# ATM9036_3P4W.net
KiCad netlist of a schematic drawn in EAGLE
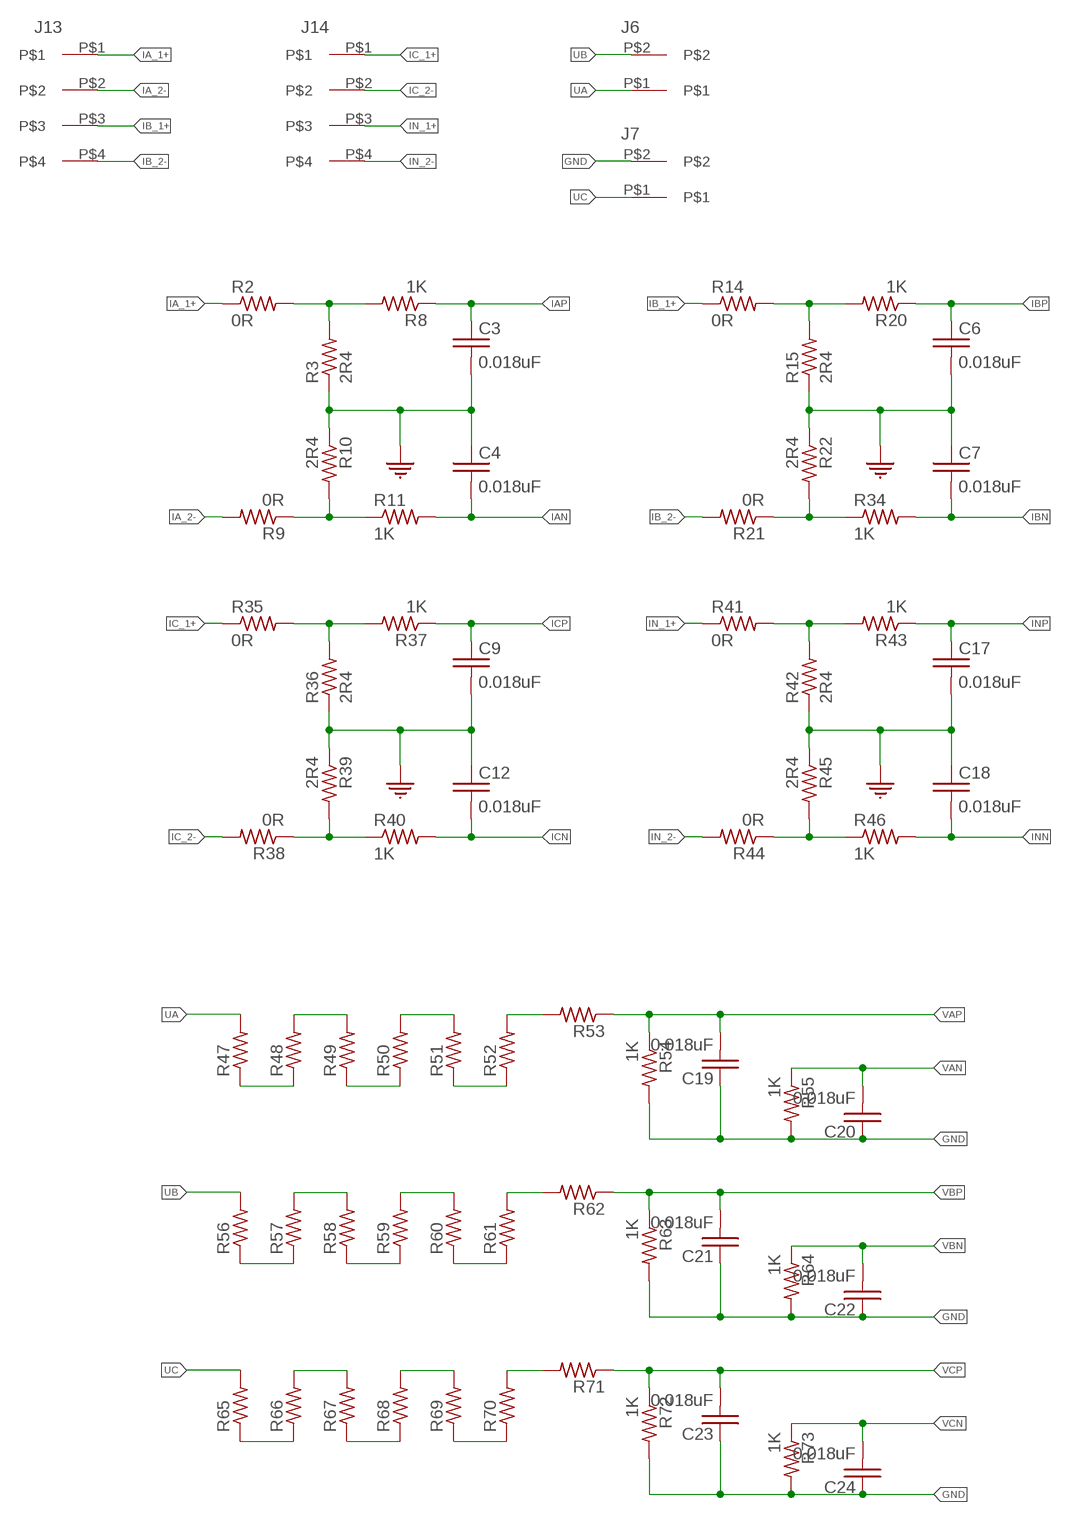
[diagram p0: schematic, sheet 1, part 1 of 2]
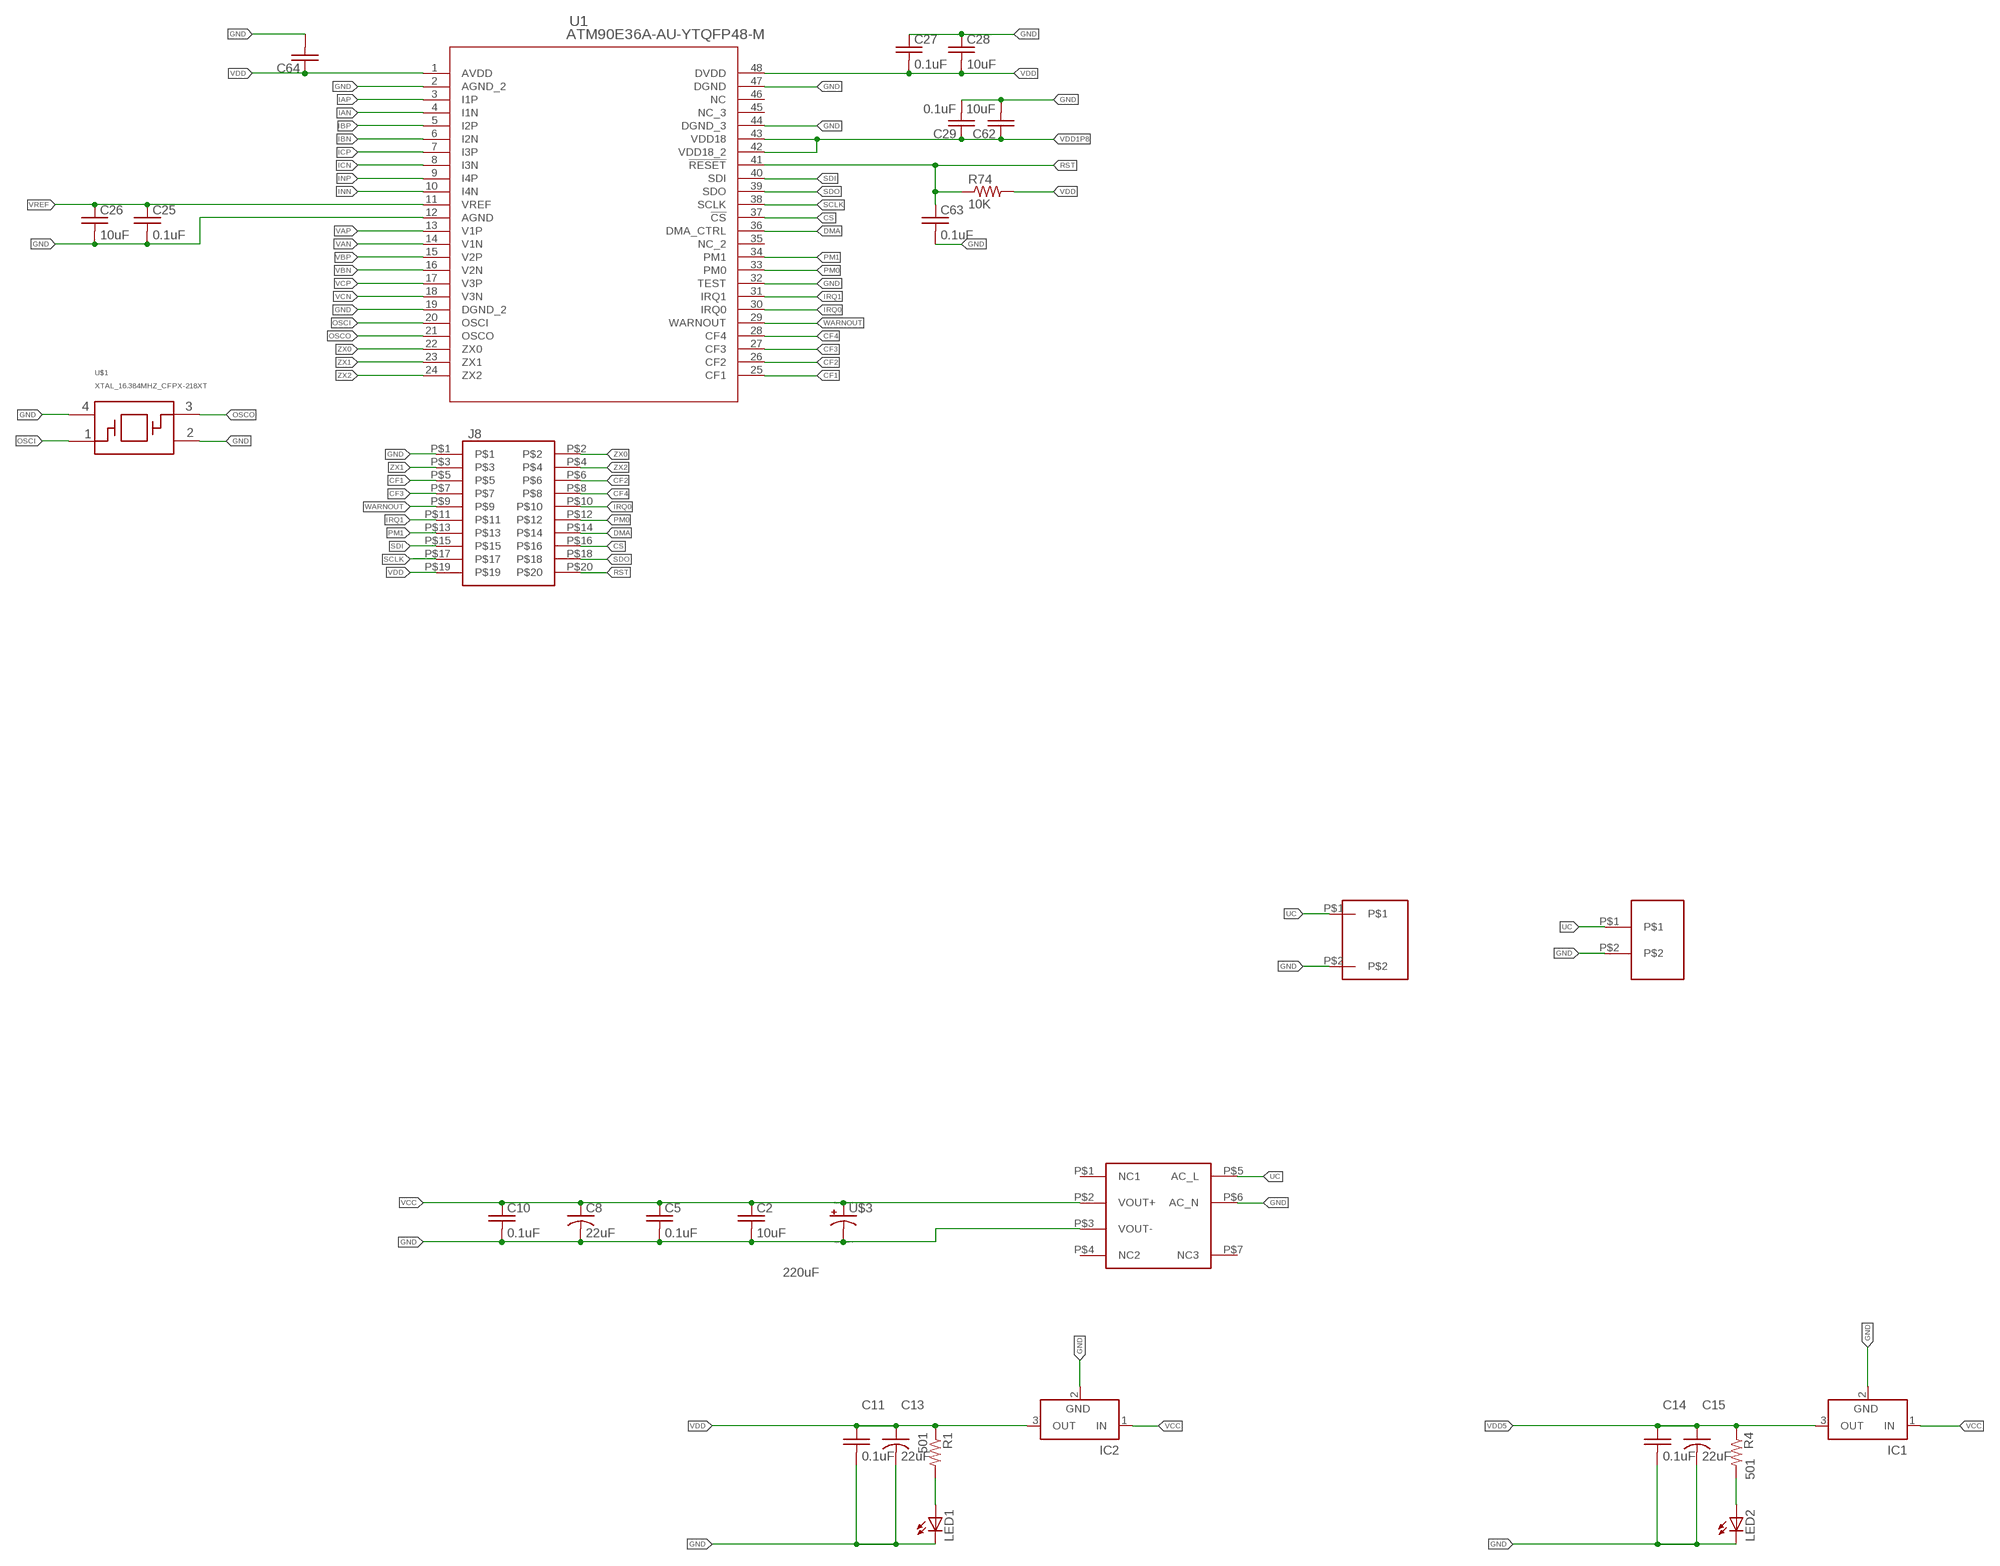
[diagram p1: schematic, sheet 1, part 2 of 2]

(export (version "E")
  (design (tool "Eeschema 10.0.6"))
  (components
    (comp (ref "C1")
      (value "CAP_THIN_FILM_TDK_32922CAP")
      (footprint "eagle-import:CAP_THIN_FILM_32922")
      (libsource (lib "eagle-import") (part "CAP_THIN_FILM_TDK_32922CAP"))
    )
    (comp (ref "C2")
      (value "10uF")
      (footprint "eagle-import:0402")
      (libsource (lib "eagle-import") (part "C_0402"))
    )
    (comp (ref "C3")
      (value "0.018uF")
      (footprint "eagle-import:0402")
      (libsource (lib "eagle-import") (part "C_0402"))
    )
    (comp (ref "C4")
      (value "0.018uF")
      (footprint "eagle-import:0402")
      (libsource (lib "eagle-import") (part "C_0402"))
    )
    (comp (ref "C5")
      (value "0.1uF")
      (footprint "eagle-import:0402")
      (libsource (lib "eagle-import") (part "C_0402"))
    )
    (comp (ref "C6")
      (value "0.018uF")
      (footprint "eagle-import:0402")
      (libsource (lib "eagle-import") (part "C_0402"))
    )
    (comp (ref "C7")
      (value "0.018uF")
      (footprint "eagle-import:0402")
      (libsource (lib "eagle-import") (part "C_0402"))
    )
    (comp (ref "C8")
      (value "22uF")
      (footprint "eagle-import:C1206")
      (libsource (lib "eagle-import") (part "C-USC1206"))
    )
    (comp (ref "C9")
      (value "0.018uF")
      (footprint "eagle-import:0402")
      (libsource (lib "eagle-import") (part "C_0402"))
    )
    (comp (ref "C10")
      (value "0.1uF")
      (footprint "eagle-import:0402")
      (libsource (lib "eagle-import") (part "C_0402"))
    )
    (comp (ref "C11")
      (value "0.1uF")
      (footprint "eagle-import:0402")
      (libsource (lib "eagle-import") (part "C_0402"))
    )
    (comp (ref "C12")
      (value "0.018uF")
      (footprint "eagle-import:0402")
      (libsource (lib "eagle-import") (part "C_0402"))
    )
    (comp (ref "C13")
      (value "22uF")
      (footprint "eagle-import:C1206")
      (libsource (lib "eagle-import") (part "C-USC1206"))
    )
    (comp (ref "C14")
      (value "0.1uF")
      (footprint "eagle-import:0402")
      (libsource (lib "eagle-import") (part "C_0402"))
    )
    (comp (ref "C15")
      (value "22uF")
      (footprint "eagle-import:C1206")
      (libsource (lib "eagle-import") (part "C-USC1206"))
    )
    (comp (ref "C17")
      (value "0.018uF")
      (footprint "eagle-import:0402")
      (libsource (lib "eagle-import") (part "C_0402"))
    )
    (comp (ref "C18")
      (value "0.018uF")
      (footprint "eagle-import:0402")
      (libsource (lib "eagle-import") (part "C_0402"))
    )
    (comp (ref "C19")
      (value "0.018uF")
      (footprint "eagle-import:0402")
      (libsource (lib "eagle-import") (part "C_0402"))
    )
    (comp (ref "C20")
      (value "0.018uF")
      (footprint "eagle-import:0402")
      (libsource (lib "eagle-import") (part "C_0402"))
    )
    (comp (ref "C21")
      (value "0.018uF")
      (footprint "eagle-import:0402")
      (libsource (lib "eagle-import") (part "C_0402"))
    )
    (comp (ref "C22")
      (value "0.018uF")
      (footprint "eagle-import:0402")
      (libsource (lib "eagle-import") (part "C_0402"))
    )
    (comp (ref "C23")
      (value "0.018uF")
      (footprint "eagle-import:0402")
      (libsource (lib "eagle-import") (part "C_0402"))
    )
    (comp (ref "C24")
      (value "0.018uF")
      (footprint "eagle-import:0402")
      (libsource (lib "eagle-import") (part "C_0402"))
    )
    (comp (ref "C25")
      (value "0.1uF")
      (footprint "eagle-import:0402")
      (libsource (lib "eagle-import") (part "C_0402"))
    )
    (comp (ref "C26")
      (value "10uF")
      (footprint "eagle-import:0402")
      (libsource (lib "eagle-import") (part "C_0402"))
    )
    (comp (ref "C27")
      (value "0.1uF")
      (footprint "eagle-import:0402")
      (libsource (lib "eagle-import") (part "C_0402"))
    )
    (comp (ref "C28")
      (value "10uF")
      (footprint "eagle-import:0402")
      (libsource (lib "eagle-import") (part "C_0402"))
    )
    (comp (ref "C29")
      (value "0.1uF")
      (footprint "eagle-import:0402")
      (libsource (lib "eagle-import") (part "C_0402"))
    )
    (comp (ref "C62")
      (value "10uF")
      (footprint "eagle-import:0402")
      (libsource (lib "eagle-import") (part "C_0402"))
    )
    (comp (ref "C63")
      (value "0.1uF")
      (footprint "eagle-import:0402")
      (libsource (lib "eagle-import") (part "C_0402"))
    )
    (comp (ref "C64")
      (value "C_0402")
      (footprint "eagle-import:0402")
      (libsource (lib "eagle-import") (part "C_0402"))
    )
    (comp (ref "IC1")
      (value "LT1129CST5")
      (footprint "eagle-import:SOT223")
      (fields (field (name "MPN") "LT1129CST-5#PBF"))
      (libsource (lib "eagle-import") (part "LT1129CST5"))
    )
    (comp (ref "IC2")
      (value "LT1129CST3")
      (footprint "eagle-import:SOT223")
      (fields (field (name "MPN") "LT1129CST-5#PBF"))
      (libsource (lib "eagle-import") (part "LT1129CST3"))
    )
    (comp (ref "J6")
      (value "3.81MM_1_X_2_RT_ANGLE_PLUG_HEADER")
      (footprint "eagle-import:2_3.81MM_PITCH")
      (libsource (lib "eagle-import") (part "3.81MM_1_X_2_RT_ANGLE_PLUG_HEADER"))
    )
    (comp (ref "J7")
      (value "3.81MM_1_X_2_RT_ANGLE_PLUG_HEADER")
      (footprint "eagle-import:2_3.81MM_PITCH")
      (libsource (lib "eagle-import") (part "3.81MM_1_X_2_RT_ANGLE_PLUG_HEADER"))
    )
    (comp (ref "J8")
      (value "2_X_10_HEADER_GENERIC")
      (footprint "eagle-import:2_X_10_.1_INCH")
      (libsource (lib "eagle-import") (part "2_X_10_HEADER_GENERIC"))
    )
    (comp (ref "J13")
      (value "3.81MM_1_X_4_RT_ANGLE_PLUG_HEADER")
      (footprint "eagle-import:1X4_3.81MM_PITCH")
      (libsource (lib "eagle-import") (part "3.81MM_1_X_4_RT_ANGLE_PLUG_HEADER"))
    )
    (comp (ref "J14")
      (value "3.81MM_1_X_4_RT_ANGLE_PLUG_HEADER")
      (footprint "eagle-import:1X4_3.81MM_PITCH")
      (libsource (lib "eagle-import") (part "3.81MM_1_X_4_RT_ANGLE_PLUG_HEADER"))
    )
    (comp (ref "LED1")
      (value "LED_0805_GREEN")
      (footprint "eagle-import:LED_0805_GREEN")
      (libsource (lib "eagle-import") (part "LED_0805_GREEN"))
    )
    (comp (ref "LED2")
      (value "LED_0805_GREEN")
      (footprint "eagle-import:LED_0805_GREEN")
      (libsource (lib "eagle-import") (part "LED_0805_GREEN"))
    )
    (comp (ref "R1")
      (value "501")
      (footprint "eagle-import:0402")
      (libsource (lib "eagle-import") (part "R_0402"))
    )
    (comp (ref "R2")
      (value "0R")
      (footprint "eagle-import:0402")
      (libsource (lib "eagle-import") (part "R_0402"))
    )
    (comp (ref "R3")
      (value "2R4")
      (footprint "eagle-import:0402")
      (libsource (lib "eagle-import") (part "R_0402"))
    )
    (comp (ref "R4")
      (value "501")
      (footprint "eagle-import:0402")
      (libsource (lib "eagle-import") (part "R_0402"))
    )
    (comp (ref "R8")
      (value "1K")
      (footprint "eagle-import:0402")
      (libsource (lib "eagle-import") (part "R_0402"))
    )
    (comp (ref "R9")
      (value "0R")
      (footprint "eagle-import:0402")
      (libsource (lib "eagle-import") (part "R_0402"))
    )
    (comp (ref "R10")
      (value "2R4")
      (footprint "eagle-import:0402")
      (libsource (lib "eagle-import") (part "R_0402"))
    )
    (comp (ref "R11")
      (value "1K")
      (footprint "eagle-import:0402")
      (libsource (lib "eagle-import") (part "R_0402"))
    )
    (comp (ref "R14")
      (value "0R")
      (footprint "eagle-import:0402")
      (libsource (lib "eagle-import") (part "R_0402"))
    )
    (comp (ref "R15")
      (value "2R4")
      (footprint "eagle-import:0402")
      (libsource (lib "eagle-import") (part "R_0402"))
    )
    (comp (ref "R20")
      (value "1K")
      (footprint "eagle-import:0402")
      (libsource (lib "eagle-import") (part "R_0402"))
    )
    (comp (ref "R21")
      (value "0R")
      (footprint "eagle-import:0402")
      (libsource (lib "eagle-import") (part "R_0402"))
    )
    (comp (ref "R22")
      (value "2R4")
      (footprint "eagle-import:0402")
      (libsource (lib "eagle-import") (part "R_0402"))
    )
    (comp (ref "R34")
      (value "1K")
      (footprint "eagle-import:0402")
      (libsource (lib "eagle-import") (part "R_0402"))
    )
    (comp (ref "R35")
      (value "0R")
      (footprint "eagle-import:0402")
      (libsource (lib "eagle-import") (part "R_0402"))
    )
    (comp (ref "R36")
      (value "2R4")
      (footprint "eagle-import:0402")
      (libsource (lib "eagle-import") (part "R_0402"))
    )
    (comp (ref "R37")
      (value "1K")
      (footprint "eagle-import:0402")
      (libsource (lib "eagle-import") (part "R_0402"))
    )
    (comp (ref "R38")
      (value "0R")
      (footprint "eagle-import:0402")
      (libsource (lib "eagle-import") (part "R_0402"))
    )
    (comp (ref "R39")
      (value "2R4")
      (footprint "eagle-import:0402")
      (libsource (lib "eagle-import") (part "R_0402"))
    )
    (comp (ref "R40")
      (value "1K")
      (footprint "eagle-import:0402")
      (libsource (lib "eagle-import") (part "R_0402"))
    )
    (comp (ref "R41")
      (value "0R")
      (footprint "eagle-import:0402")
      (libsource (lib "eagle-import") (part "R_0402"))
    )
    (comp (ref "R42")
      (value "2R4")
      (footprint "eagle-import:0402")
      (libsource (lib "eagle-import") (part "R_0402"))
    )
    (comp (ref "R43")
      (value "1K")
      (footprint "eagle-import:0402")
      (libsource (lib "eagle-import") (part "R_0402"))
    )
    (comp (ref "R44")
      (value "0R")
      (footprint "eagle-import:0402")
      (libsource (lib "eagle-import") (part "R_0402"))
    )
    (comp (ref "R45")
      (value "2R4")
      (footprint "eagle-import:0402")
      (libsource (lib "eagle-import") (part "R_0402"))
    )
    (comp (ref "R46")
      (value "1K")
      (footprint "eagle-import:0402")
      (libsource (lib "eagle-import") (part "R_0402"))
    )
    (comp (ref "R47")
      (value "R_0402")
      (footprint "eagle-import:0402")
      (libsource (lib "eagle-import") (part "R_0402"))
    )
    (comp (ref "R48")
      (value "R_0402")
      (footprint "eagle-import:0402")
      (libsource (lib "eagle-import") (part "R_0402"))
    )
    (comp (ref "R49")
      (value "R_0402")
      (footprint "eagle-import:0402")
      (libsource (lib "eagle-import") (part "R_0402"))
    )
    (comp (ref "R50")
      (value "R_0402")
      (footprint "eagle-import:0402")
      (libsource (lib "eagle-import") (part "R_0402"))
    )
    (comp (ref "R51")
      (value "R_0402")
      (footprint "eagle-import:0402")
      (libsource (lib "eagle-import") (part "R_0402"))
    )
    (comp (ref "R52")
      (value "R_0402")
      (footprint "eagle-import:0402")
      (libsource (lib "eagle-import") (part "R_0402"))
    )
    (comp (ref "R53")
      (value "R_0402")
      (footprint "eagle-import:0402")
      (libsource (lib "eagle-import") (part "R_0402"))
    )
    (comp (ref "R54")
      (value "1K")
      (footprint "eagle-import:0402")
      (libsource (lib "eagle-import") (part "R_0402"))
    )
    (comp (ref "R55")
      (value "1K")
      (footprint "eagle-import:0402")
      (libsource (lib "eagle-import") (part "R_0402"))
    )
    (comp (ref "R56")
      (value "R_0402")
      (footprint "eagle-import:0402")
      (libsource (lib "eagle-import") (part "R_0402"))
    )
    (comp (ref "R57")
      (value "R_0402")
      (footprint "eagle-import:0402")
      (libsource (lib "eagle-import") (part "R_0402"))
    )
    (comp (ref "R58")
      (value "R_0402")
      (footprint "eagle-import:0402")
      (libsource (lib "eagle-import") (part "R_0402"))
    )
    (comp (ref "R59")
      (value "R_0402")
      (footprint "eagle-import:0402")
      (libsource (lib "eagle-import") (part "R_0402"))
    )
    (comp (ref "R60")
      (value "R_0402")
      (footprint "eagle-import:0402")
      (libsource (lib "eagle-import") (part "R_0402"))
    )
    (comp (ref "R61")
      (value "R_0402")
      (footprint "eagle-import:0402")
      (libsource (lib "eagle-import") (part "R_0402"))
    )
    (comp (ref "R62")
      (value "R_0402")
      (footprint "eagle-import:0402")
      (libsource (lib "eagle-import") (part "R_0402"))
    )
    (comp (ref "R63")
      (value "1K")
      (footprint "eagle-import:0402")
      (libsource (lib "eagle-import") (part "R_0402"))
    )
    (comp (ref "R64")
      (value "1K")
      (footprint "eagle-import:0402")
      (libsource (lib "eagle-import") (part "R_0402"))
    )
    (comp (ref "R65")
      (value "R_0402")
      (footprint "eagle-import:0402")
      (libsource (lib "eagle-import") (part "R_0402"))
    )
    (comp (ref "R66")
      (value "R_0402")
      (footprint "eagle-import:0402")
      (libsource (lib "eagle-import") (part "R_0402"))
    )
    (comp (ref "R67")
      (value "R_0402")
      (footprint "eagle-import:0402")
      (libsource (lib "eagle-import") (part "R_0402"))
    )
    (comp (ref "R68")
      (value "R_0402")
      (footprint "eagle-import:0402")
      (libsource (lib "eagle-import") (part "R_0402"))
    )
    (comp (ref "R69")
      (value "R_0402")
      (footprint "eagle-import:0402")
      (libsource (lib "eagle-import") (part "R_0402"))
    )
    (comp (ref "R70")
      (value "R_0402")
      (footprint "eagle-import:0402")
      (libsource (lib "eagle-import") (part "R_0402"))
    )
    (comp (ref "R71")
      (value "R_0402")
      (footprint "eagle-import:0402")
      (libsource (lib "eagle-import") (part "R_0402"))
    )
    (comp (ref "R72")
      (value "1K")
      (footprint "eagle-import:0402")
      (libsource (lib "eagle-import") (part "R_0402"))
    )
    (comp (ref "R73")
      (value "1K")
      (footprint "eagle-import:0402")
      (libsource (lib "eagle-import") (part "R_0402"))
    )
    (comp (ref "R74")
      (value "10K")
      (footprint "eagle-import:0402")
      (libsource (lib "eagle-import") (part "R_0402"))
    )
    (comp (ref "U$1")
      (value "XTAL_16.384MHZ_CFPX-218XT")
      (footprint "eagle-import:XTAL_2.5X2.0")
      (libsource (lib "eagle-import") (part "XTAL_16.384MHZ_CFPX-218XT"))
    )
    (comp (ref "U$2")
      (value "VAR_10MM_VDRUS10")
      (footprint "eagle-import:VAR_10MM_VDRUS10")
      (libsource (lib "eagle-import") (part "VAR_10MM_VDRUS10"))
    )
    (comp (ref "U$3")
      (value "220uF")
      (footprint "eagle-import:C_AL_ELECTROLYTIC_SMD_220UF")
      (libsource (lib "eagle-import") (part "C_AL_ELECTROLYTIC_SMD_220UF"))
    )
    (comp (ref "U1")
      (value "ATM90E36A-AU-YTQFP48-M")
      (footprint "eagle-import:TQFP48-M")
      (fields (field (name "MANUFACTURER_PART_NUMBER") "ATM90E36AAUY"))
      (libsource (lib "eagle-import") (part "ATM90E36A-AU-YTQFP48-M"))
    )
    (comp (ref "U2")
      (value "TMLM_04109")
      (footprint "eagle-import:TMLM04")
      (libsource (lib "eagle-import") (part "TMLM_04109"))
    )
  )
  (nets
    (net (code "1") (name "CF1") (class "Default")
      (node (ref "J8") (pin "P$5") (pinfunction "P$5_P$5") (pintype "bidirectional"))
      (node (ref "U1") (pin "25") (pinfunction "CF1_25") (pintype "output"))
    )
    (net (code "2") (name "CF2") (class "Default")
      (node (ref "J8") (pin "P$6") (pinfunction "P$6_P$6") (pintype "bidirectional"))
      (node (ref "U1") (pin "26") (pinfunction "CF2_26") (pintype "output"))
    )
    (net (code "3") (name "CF3") (class "Default")
      (node (ref "J8") (pin "P$7") (pinfunction "P$7_P$7") (pintype "bidirectional"))
      (node (ref "U1") (pin "27") (pinfunction "CF3_27") (pintype "output"))
    )
    (net (code "4") (name "CF4") (class "Default")
      (node (ref "J8") (pin "P$8") (pinfunction "P$8_P$8") (pintype "bidirectional"))
      (node (ref "U1") (pin "28") (pinfunction "CF4_28") (pintype "output"))
    )
    (net (code "5") (name "CS") (class "Default")
      (node (ref "J8") (pin "P$16") (pinfunction "P$16_P$16") (pintype "bidirectional"))
      (node (ref "U1") (pin "37") (pinfunction "~{CS}_37") (pintype "bidirectional"))
    )
    (net (code "6") (name "DMA") (class "Default")
      (node (ref "J8") (pin "P$14") (pinfunction "P$14_P$14") (pintype "bidirectional"))
      (node (ref "U1") (pin "36") (pinfunction "DMA_CTRL_36") (pintype "input"))
    )
    (net (code "7") (name "GND") (class "Default")
      (node (ref "C1") (pin "P$2") (pinfunction "P$2_P$2") (pintype "bidirectional"))
      (node (ref "C10") (pin "P$2") (pinfunction "2_P$2") (pintype "passive"))
      (node (ref "C11") (pin "P$2") (pinfunction "2_P$2") (pintype "passive"))
      (node (ref "C12") (pin "P$1") (pinfunction "1_P$1") (pintype "passive"))
      (node (ref "C13") (pin "2") (pinfunction "2_2") (pintype "passive"))
      (node (ref "C14") (pin "P$2") (pinfunction "2_P$2") (pintype "passive"))
      (node (ref "C15") (pin "2") (pinfunction "2_2") (pintype "passive"))
      (node (ref "C17") (pin "P$2") (pinfunction "2_P$2") (pintype "passive"))
      (node (ref "C18") (pin "P$1") (pinfunction "1_P$1") (pintype "passive"))
      (node (ref "C19") (pin "P$1") (pinfunction "1_P$1") (pintype "passive"))
      (node (ref "C2") (pin "P$2") (pinfunction "2_P$2") (pintype "passive"))
      (node (ref "C20") (pin "P$1") (pinfunction "1_P$1") (pintype "passive"))
      (node (ref "C21") (pin "P$1") (pinfunction "1_P$1") (pintype "passive"))
      (node (ref "C22") (pin "P$1") (pinfunction "1_P$1") (pintype "passive"))
      (node (ref "C23") (pin "P$1") (pinfunction "1_P$1") (pintype "passive"))
      (node (ref "C24") (pin "P$1") (pinfunction "1_P$1") (pintype "passive"))
      (node (ref "C25") (pin "P$2") (pinfunction "2_P$2") (pintype "passive"))
      (node (ref "C26") (pin "P$2") (pinfunction "2_P$2") (pintype "passive"))
      (node (ref "C27") (pin "P$1") (pinfunction "1_P$1") (pintype "passive"))
      (node (ref "C28") (pin "P$1") (pinfunction "1_P$1") (pintype "passive"))
      (node (ref "C29") (pin "P$2") (pinfunction "2_P$2") (pintype "passive"))
      (node (ref "C3") (pin "P$2") (pinfunction "2_P$2") (pintype "passive"))
      (node (ref "C4") (pin "P$1") (pinfunction "1_P$1") (pintype "passive"))
      (node (ref "C5") (pin "P$2") (pinfunction "2_P$2") (pintype "passive"))
      (node (ref "C6") (pin "P$2") (pinfunction "2_P$2") (pintype "passive"))
      (node (ref "C62") (pin "P$2") (pinfunction "2_P$2") (pintype "passive"))
      (node (ref "C63") (pin "P$2") (pinfunction "2_P$2") (pintype "passive"))
      (node (ref "C64") (pin "P$2") (pinfunction "2_P$2") (pintype "passive"))
      (node (ref "C7") (pin "P$1") (pinfunction "1_P$1") (pintype "passive"))
      (node (ref "C8") (pin "2") (pinfunction "2_2") (pintype "passive"))
      (node (ref "C9") (pin "P$2") (pinfunction "2_P$2") (pintype "passive"))
      (node (ref "IC1") (pin "2") (pinfunction "GND_2") (pintype "power_in"))
      (node (ref "IC2") (pin "2") (pinfunction "GND_2") (pintype "power_in"))
      (node (ref "J7") (pin "P$2") (pinfunction "P$2_P$2") (pintype "bidirectional"))
      (node (ref "J8") (pin "P$1") (pinfunction "P$1_P$1") (pintype "bidirectional"))
      (node (ref "LED1") (pin "C") (pinfunction "C_C") (pintype "passive"))
      (node (ref "LED2") (pin "C") (pinfunction "C_C") (pintype "passive"))
      (node (ref "R10") (pin "P$1") (pinfunction "1_P$1") (pintype "passive"))
      (node (ref "R15") (pin "P$1") (pinfunction "1_P$1") (pintype "passive"))
      (node (ref "R22") (pin "P$1") (pinfunction "1_P$1") (pintype "passive"))
      (node (ref "R3") (pin "P$1") (pinfunction "1_P$1") (pintype "passive"))
      (node (ref "R36") (pin "P$1") (pinfunction "1_P$1") (pintype "passive"))
      (node (ref "R39") (pin "P$1") (pinfunction "1_P$1") (pintype "passive"))
      (node (ref "R42") (pin "P$1") (pinfunction "1_P$1") (pintype "passive"))
      (node (ref "R45") (pin "P$1") (pinfunction "1_P$1") (pintype "passive"))
      (node (ref "R54") (pin "P$2") (pinfunction "2_P$2") (pintype "passive"))
      (node (ref "R55") (pin "P$2") (pinfunction "2_P$2") (pintype "passive"))
      (node (ref "R63") (pin "P$2") (pinfunction "2_P$2") (pintype "passive"))
      (node (ref "R64") (pin "P$2") (pinfunction "2_P$2") (pintype "passive"))
      (node (ref "R72") (pin "P$2") (pinfunction "2_P$2") (pintype "passive"))
      (node (ref "R73") (pin "P$2") (pinfunction "2_P$2") (pintype "passive"))
      (node (ref "U$1") (pin "2") (pinfunction "2_2") (pintype "bidirectional"))
      (node (ref "U$1") (pin "4") (pinfunction "4_4") (pintype "bidirectional"))
      (node (ref "U$2") (pin "P$2") (pinfunction "P$2_P$2") (pintype "bidirectional"))
      (node (ref "U$3") (pin "N-") (pinfunction "-_N-") (pintype "passive"))
      (node (ref "U1") (pin "12") (pinfunction "AGND_12") (pintype "power_in"))
      (node (ref "U1") (pin "19") (pinfunction "DGND_2_19") (pintype "power_in"))
      (node (ref "U1") (pin "2") (pinfunction "AGND_2_2") (pintype "power_in"))
      (node (ref "U1") (pin "32") (pinfunction "TEST_32") (pintype "input"))
      (node (ref "U1") (pin "44") (pinfunction "DGND_3_44") (pintype "power_in"))
      (node (ref "U1") (pin "47") (pinfunction "DGND_47") (pintype "power_in"))
      (node (ref "U2") (pin "P$3") (pinfunction "VOUT-_P$3") (pintype "bidirectional"))
      (node (ref "U2") (pin "P$6") (pinfunction "AC_N_P$6") (pintype "bidirectional"))
    )
    (net (code "8") (name "IAN") (class "Default")
      (node (ref "C4") (pin "P$2") (pinfunction "2_P$2") (pintype "passive"))
      (node (ref "R11") (pin "P$2") (pinfunction "2_P$2") (pintype "passive"))
      (node (ref "U1") (pin "4") (pinfunction "I1N_4") (pintype "input"))
    )
    (net (code "9") (name "IAP") (class "Default")
      (node (ref "C3") (pin "P$1") (pinfunction "1_P$1") (pintype "passive"))
      (node (ref "R8") (pin "P$1") (pinfunction "1_P$1") (pintype "passive"))
      (node (ref "U1") (pin "3") (pinfunction "I1P_3") (pintype "input"))
    )
    (net (code "10") (name "IA_1+") (class "Default")
      (node (ref "J13") (pin "P$1") (pinfunction "P$1_P$1") (pintype "bidirectional"))
      (node (ref "R2") (pin "P$1") (pinfunction "1_P$1") (pintype "passive"))
    )
    (net (code "11") (name "IA_2-") (class "Default")
      (node (ref "J13") (pin "P$2") (pinfunction "P$2_P$2") (pintype "bidirectional"))
      (node (ref "R9") (pin "P$2") (pinfunction "2_P$2") (pintype "passive"))
    )
    (net (code "12") (name "IBN") (class "Default")
      (node (ref "C7") (pin "P$2") (pinfunction "2_P$2") (pintype "passive"))
      (node (ref "R34") (pin "P$2") (pinfunction "2_P$2") (pintype "passive"))
      (node (ref "U1") (pin "6") (pinfunction "I2N_6") (pintype "input"))
    )
    (net (code "13") (name "IBP") (class "Default")
      (node (ref "C6") (pin "P$1") (pinfunction "1_P$1") (pintype "passive"))
      (node (ref "R20") (pin "P$1") (pinfunction "1_P$1") (pintype "passive"))
      (node (ref "U1") (pin "5") (pinfunction "I2P_5") (pintype "input"))
    )
    (net (code "14") (name "IB_1+") (class "Default")
      (node (ref "J13") (pin "P$3") (pinfunction "P$3_P$3") (pintype "bidirectional"))
      (node (ref "R14") (pin "P$1") (pinfunction "1_P$1") (pintype "passive"))
    )
    (net (code "15") (name "IB_2-") (class "Default")
      (node (ref "J13") (pin "P$4") (pinfunction "P$4_P$4") (pintype "bidirectional"))
      (node (ref "R21") (pin "P$2") (pinfunction "2_P$2") (pintype "passive"))
    )
    (net (code "16") (name "ICN") (class "Default")
      (node (ref "C12") (pin "P$2") (pinfunction "2_P$2") (pintype "passive"))
      (node (ref "R40") (pin "P$2") (pinfunction "2_P$2") (pintype "passive"))
      (node (ref "U1") (pin "8") (pinfunction "I3N_8") (pintype "input"))
    )
    (net (code "17") (name "ICP") (class "Default")
      (node (ref "C9") (pin "P$1") (pinfunction "1_P$1") (pintype "passive"))
      (node (ref "R37") (pin "P$1") (pinfunction "1_P$1") (pintype "passive"))
      (node (ref "U1") (pin "7") (pinfunction "I3P_7") (pintype "input"))
    )
    (net (code "18") (name "IC_1+") (class "Default")
      (node (ref "J14") (pin "P$1") (pinfunction "P$1_P$1") (pintype "bidirectional"))
      (node (ref "R35") (pin "P$1") (pinfunction "1_P$1") (pintype "passive"))
    )
    (net (code "19") (name "IC_2-") (class "Default")
      (node (ref "J14") (pin "P$2") (pinfunction "P$2_P$2") (pintype "bidirectional"))
      (node (ref "R38") (pin "P$2") (pinfunction "2_P$2") (pintype "passive"))
    )
    (net (code "20") (name "INN") (class "Default")
      (node (ref "C18") (pin "P$2") (pinfunction "2_P$2") (pintype "passive"))
      (node (ref "R46") (pin "P$2") (pinfunction "2_P$2") (pintype "passive"))
      (node (ref "U1") (pin "10") (pinfunction "I4N_10") (pintype "input"))
    )
    (net (code "21") (name "INP") (class "Default")
      (node (ref "C17") (pin "P$1") (pinfunction "1_P$1") (pintype "passive"))
      (node (ref "R43") (pin "P$1") (pinfunction "1_P$1") (pintype "passive"))
      (node (ref "U1") (pin "9") (pinfunction "I4P_9") (pintype "input"))
    )
    (net (code "22") (name "IN_1+") (class "Default")
      (node (ref "J14") (pin "P$3") (pinfunction "P$3_P$3") (pintype "bidirectional"))
      (node (ref "R41") (pin "P$1") (pinfunction "1_P$1") (pintype "passive"))
    )
    (net (code "23") (name "IN_2-") (class "Default")
      (node (ref "J14") (pin "P$4") (pinfunction "P$4_P$4") (pintype "bidirectional"))
      (node (ref "R44") (pin "P$2") (pinfunction "2_P$2") (pintype "passive"))
    )
    (net (code "24") (name "IRQ0") (class "Default")
      (node (ref "J8") (pin "P$10") (pinfunction "P$10_P$10") (pintype "bidirectional"))
      (node (ref "U1") (pin "30") (pinfunction "IRQ0_30") (pintype "output"))
    )
    (net (code "25") (name "IRQ1") (class "Default")
      (node (ref "J8") (pin "P$11") (pinfunction "P$11_P$11") (pintype "bidirectional"))
      (node (ref "U1") (pin "31") (pinfunction "IRQ1_31") (pintype "output"))
    )
    (net (code "26") (name "Net-(R1-2)") (class "Default")
      (node (ref "LED1") (pin "A") (pinfunction "A_A") (pintype "passive"))
      (node (ref "R1") (pin "P$2") (pinfunction "2_P$2") (pintype "passive"))
    )
    (net (code "27") (name "Net-(R2-2)") (class "Default")
      (node (ref "R2") (pin "P$2") (pinfunction "2_P$2") (pintype "passive"))
      (node (ref "R3") (pin "P$2") (pinfunction "2_P$2") (pintype "passive"))
      (node (ref "R8") (pin "P$2") (pinfunction "2_P$2") (pintype "passive"))
    )
    (net (code "28") (name "Net-(R4-2)") (class "Default")
      (node (ref "LED2") (pin "A") (pinfunction "A_A") (pintype "passive"))
      (node (ref "R4") (pin "P$2") (pinfunction "2_P$2") (pintype "passive"))
    )
    (net (code "29") (name "Net-(R10-2)") (class "Default")
      (node (ref "R10") (pin "P$2") (pinfunction "2_P$2") (pintype "passive"))
      (node (ref "R11") (pin "P$1") (pinfunction "1_P$1") (pintype "passive"))
      (node (ref "R9") (pin "P$1") (pinfunction "1_P$1") (pintype "passive"))
    )
    (net (code "30") (name "Net-(R14-2)") (class "Default")
      (node (ref "R14") (pin "P$2") (pinfunction "2_P$2") (pintype "passive"))
      (node (ref "R15") (pin "P$2") (pinfunction "2_P$2") (pintype "passive"))
      (node (ref "R20") (pin "P$2") (pinfunction "2_P$2") (pintype "passive"))
    )
    (net (code "31") (name "Net-(R21-1)") (class "Default")
      (node (ref "R21") (pin "P$1") (pinfunction "1_P$1") (pintype "passive"))
      (node (ref "R22") (pin "P$2") (pinfunction "2_P$2") (pintype "passive"))
      (node (ref "R34") (pin "P$1") (pinfunction "1_P$1") (pintype "passive"))
    )
    (net (code "32") (name "Net-(R35-2)") (class "Default")
      (node (ref "R35") (pin "P$2") (pinfunction "2_P$2") (pintype "passive"))
      (node (ref "R36") (pin "P$2") (pinfunction "2_P$2") (pintype "passive"))
      (node (ref "R37") (pin "P$2") (pinfunction "2_P$2") (pintype "passive"))
    )
    (net (code "33") (name "Net-(R38-1)") (class "Default")
      (node (ref "R38") (pin "P$1") (pinfunction "1_P$1") (pintype "passive"))
      (node (ref "R39") (pin "P$2") (pinfunction "2_P$2") (pintype "passive"))
      (node (ref "R40") (pin "P$1") (pinfunction "1_P$1") (pintype "passive"))
    )
    (net (code "34") (name "Net-(R41-2)") (class "Default")
      (node (ref "R41") (pin "P$2") (pinfunction "2_P$2") (pintype "passive"))
      (node (ref "R42") (pin "P$2") (pinfunction "2_P$2") (pintype "passive"))
      (node (ref "R43") (pin "P$2") (pinfunction "2_P$2") (pintype "passive"))
    )
    (net (code "35") (name "Net-(R44-1)") (class "Default")
      (node (ref "R44") (pin "P$1") (pinfunction "1_P$1") (pintype "passive"))
      (node (ref "R45") (pin "P$2") (pinfunction "2_P$2") (pintype "passive"))
      (node (ref "R46") (pin "P$1") (pinfunction "1_P$1") (pintype "passive"))
    )
    (net (code "36") (name "Net-(R47-1)") (class "Default")
      (node (ref "R47") (pin "P$1") (pinfunction "1_P$1") (pintype "passive"))
      (node (ref "R48") (pin "P$1") (pinfunction "1_P$1") (pintype "passive"))
    )
    (net (code "37") (name "Net-(R48-2)") (class "Default")
      (node (ref "R48") (pin "P$2") (pinfunction "2_P$2") (pintype "passive"))
      (node (ref "R49") (pin "P$2") (pinfunction "2_P$2") (pintype "passive"))
    )
    (net (code "38") (name "Net-(R49-1)") (class "Default")
      (node (ref "R49") (pin "P$1") (pinfunction "1_P$1") (pintype "passive"))
      (node (ref "R50") (pin "P$1") (pinfunction "1_P$1") (pintype "passive"))
    )
    (net (code "39") (name "Net-(R50-2)") (class "Default")
      (node (ref "R50") (pin "P$2") (pinfunction "2_P$2") (pintype "passive"))
      (node (ref "R51") (pin "P$2") (pinfunction "2_P$2") (pintype "passive"))
    )
    (net (code "40") (name "Net-(R51-1)") (class "Default")
      (node (ref "R51") (pin "P$1") (pinfunction "1_P$1") (pintype "passive"))
      (node (ref "R52") (pin "P$1") (pinfunction "1_P$1") (pintype "passive"))
    )
    (net (code "41") (name "Net-(R52-2)") (class "Default")
      (node (ref "R52") (pin "P$2") (pinfunction "2_P$2") (pintype "passive"))
      (node (ref "R53") (pin "P$2") (pinfunction "2_P$2") (pintype "passive"))
    )
    (net (code "42") (name "Net-(R56-1)") (class "Default")
      (node (ref "R56") (pin "P$1") (pinfunction "1_P$1") (pintype "passive"))
      (node (ref "R57") (pin "P$1") (pinfunction "1_P$1") (pintype "passive"))
    )
    (net (code "43") (name "Net-(R57-2)") (class "Default")
      (node (ref "R57") (pin "P$2") (pinfunction "2_P$2") (pintype "passive"))
      (node (ref "R58") (pin "P$2") (pinfunction "2_P$2") (pintype "passive"))
    )
    (net (code "44") (name "Net-(R58-1)") (class "Default")
      (node (ref "R58") (pin "P$1") (pinfunction "1_P$1") (pintype "passive"))
      (node (ref "R59") (pin "P$1") (pinfunction "1_P$1") (pintype "passive"))
    )
    (net (code "45") (name "Net-(R59-2)") (class "Default")
      (node (ref "R59") (pin "P$2") (pinfunction "2_P$2") (pintype "passive"))
      (node (ref "R60") (pin "P$2") (pinfunction "2_P$2") (pintype "passive"))
    )
    (net (code "46") (name "Net-(R60-1)") (class "Default")
      (node (ref "R60") (pin "P$1") (pinfunction "1_P$1") (pintype "passive"))
      (node (ref "R61") (pin "P$1") (pinfunction "1_P$1") (pintype "passive"))
    )
    (net (code "47") (name "Net-(R61-2)") (class "Default")
      (node (ref "R61") (pin "P$2") (pinfunction "2_P$2") (pintype "passive"))
      (node (ref "R62") (pin "P$2") (pinfunction "2_P$2") (pintype "passive"))
    )
    (net (code "48") (name "Net-(R65-1)") (class "Default")
      (node (ref "R65") (pin "P$1") (pinfunction "1_P$1") (pintype "passive"))
      (node (ref "R66") (pin "P$1") (pinfunction "1_P$1") (pintype "passive"))
    )
    (net (code "49") (name "Net-(R66-2)") (class "Default")
      (node (ref "R66") (pin "P$2") (pinfunction "2_P$2") (pintype "passive"))
      (node (ref "R67") (pin "P$2") (pinfunction "2_P$2") (pintype "passive"))
    )
    (net (code "50") (name "Net-(R67-1)") (class "Default")
      (node (ref "R67") (pin "P$1") (pinfunction "1_P$1") (pintype "passive"))
      (node (ref "R68") (pin "P$1") (pinfunction "1_P$1") (pintype "passive"))
    )
    (net (code "51") (name "Net-(R68-2)") (class "Default")
      (node (ref "R68") (pin "P$2") (pinfunction "2_P$2") (pintype "passive"))
      (node (ref "R69") (pin "P$2") (pinfunction "2_P$2") (pintype "passive"))
    )
    (net (code "52") (name "Net-(R69-1)") (class "Default")
      (node (ref "R69") (pin "P$1") (pinfunction "1_P$1") (pintype "passive"))
      (node (ref "R70") (pin "P$1") (pinfunction "1_P$1") (pintype "passive"))
    )
    (net (code "53") (name "Net-(R70-2)") (class "Default")
      (node (ref "R70") (pin "P$2") (pinfunction "2_P$2") (pintype "passive"))
      (node (ref "R71") (pin "P$2") (pinfunction "2_P$2") (pintype "passive"))
    )
    (net (code "54") (name "OSCI") (class "Default")
      (node (ref "U$1") (pin "1") (pinfunction "1_1") (pintype "bidirectional"))
      (node (ref "U1") (pin "20") (pinfunction "OSCI_20") (pintype "input"))
    )
    (net (code "55") (name "OSCO") (class "Default")
      (node (ref "U$1") (pin "3") (pinfunction "3_3") (pintype "bidirectional"))
      (node (ref "U1") (pin "21") (pinfunction "OSCO_21") (pintype "output"))
    )
    (net (code "56") (name "PM0") (class "Default")
      (node (ref "J8") (pin "P$12") (pinfunction "P$12_P$12") (pintype "bidirectional"))
      (node (ref "U1") (pin "33") (pinfunction "PM0_33") (pintype "input"))
    )
    (net (code "57") (name "PM1") (class "Default")
      (node (ref "J8") (pin "P$13") (pinfunction "P$13_P$13") (pintype "bidirectional"))
      (node (ref "U1") (pin "34") (pinfunction "PM1_34") (pintype "input"))
    )
    (net (code "58") (name "RST") (class "Default")
      (node (ref "C63") (pin "P$1") (pinfunction "1_P$1") (pintype "passive"))
      (node (ref "J8") (pin "P$20") (pinfunction "P$20_P$20") (pintype "bidirectional"))
      (node (ref "R74") (pin "P$1") (pinfunction "1_P$1") (pintype "passive"))
      (node (ref "U1") (pin "41") (pinfunction "~{RESET}_41") (pintype "input"))
    )
    (net (code "59") (name "SCLK") (class "Default")
      (node (ref "J8") (pin "P$17") (pinfunction "P$17_P$17") (pintype "bidirectional"))
      (node (ref "U1") (pin "38") (pinfunction "SCLK_38") (pintype "bidirectional"))
    )
    (net (code "60") (name "SDI") (class "Default")
      (node (ref "J8") (pin "P$15") (pinfunction "P$15_P$15") (pintype "bidirectional"))
      (node (ref "U1") (pin "40") (pinfunction "SDI_40") (pintype "bidirectional"))
    )
    (net (code "61") (name "SDO") (class "Default")
      (node (ref "J8") (pin "P$18") (pinfunction "P$18_P$18") (pintype "bidirectional"))
      (node (ref "U1") (pin "39") (pinfunction "SDO_39") (pintype "bidirectional"))
    )
    (net (code "62") (name "UA") (class "Default")
      (node (ref "J6") (pin "P$1") (pinfunction "P$1_P$1") (pintype "bidirectional"))
      (node (ref "R47") (pin "P$2") (pinfunction "2_P$2") (pintype "passive"))
    )
    (net (code "63") (name "UB") (class "Default")
      (node (ref "J6") (pin "P$2") (pinfunction "P$2_P$2") (pintype "bidirectional"))
      (node (ref "R56") (pin "P$2") (pinfunction "2_P$2") (pintype "passive"))
    )
    (net (code "64") (name "UC") (class "Default")
      (node (ref "C1") (pin "P$1") (pinfunction "P$1_P$1") (pintype "bidirectional"))
      (node (ref "J7") (pin "P$1") (pinfunction "P$1_P$1") (pintype "bidirectional"))
      (node (ref "R65") (pin "P$2") (pinfunction "2_P$2") (pintype "passive"))
      (node (ref "U$2") (pin "P$1") (pinfunction "P$1_P$1") (pintype "bidirectional"))
      (node (ref "U2") (pin "P$5") (pinfunction "AC_L_P$5") (pintype "bidirectional"))
    )
    (net (code "65") (name "VAN") (class "Default")
      (node (ref "C20") (pin "P$2") (pinfunction "2_P$2") (pintype "passive"))
      (node (ref "R55") (pin "P$1") (pinfunction "1_P$1") (pintype "passive"))
      (node (ref "U1") (pin "14") (pinfunction "V1N_14") (pintype "input"))
    )
    (net (code "66") (name "VAP") (class "Default")
      (node (ref "C19") (pin "P$2") (pinfunction "2_P$2") (pintype "passive"))
      (node (ref "R53") (pin "P$1") (pinfunction "1_P$1") (pintype "passive"))
      (node (ref "R54") (pin "P$1") (pinfunction "1_P$1") (pintype "passive"))
      (node (ref "U1") (pin "13") (pinfunction "V1P_13") (pintype "input"))
    )
    (net (code "67") (name "VBN") (class "Default")
      (node (ref "C22") (pin "P$2") (pinfunction "2_P$2") (pintype "passive"))
      (node (ref "R64") (pin "P$1") (pinfunction "1_P$1") (pintype "passive"))
      (node (ref "U1") (pin "16") (pinfunction "V2N_16") (pintype "input"))
    )
    (net (code "68") (name "VBP") (class "Default")
      (node (ref "C21") (pin "P$2") (pinfunction "2_P$2") (pintype "passive"))
      (node (ref "R62") (pin "P$1") (pinfunction "1_P$1") (pintype "passive"))
      (node (ref "R63") (pin "P$1") (pinfunction "1_P$1") (pintype "passive"))
      (node (ref "U1") (pin "15") (pinfunction "V2P_15") (pintype "input"))
    )
    (net (code "69") (name "VCC") (class "Default")
      (node (ref "C10") (pin "P$1") (pinfunction "1_P$1") (pintype "passive"))
      (node (ref "C2") (pin "P$1") (pinfunction "1_P$1") (pintype "passive"))
      (node (ref "C5") (pin "P$1") (pinfunction "1_P$1") (pintype "passive"))
      (node (ref "C8") (pin "1") (pinfunction "1_1") (pintype "passive"))
      (node (ref "IC1") (pin "1") (pinfunction "IN_1") (pintype "input"))
      (node (ref "IC2") (pin "1") (pinfunction "IN_1") (pintype "input"))
      (node (ref "U$3") (pin "P+") (pinfunction "+_P+") (pintype "passive"))
      (node (ref "U2") (pin "P$2") (pinfunction "VOUT+_P$2") (pintype "bidirectional"))
    )
    (net (code "70") (name "VCN") (class "Default")
      (node (ref "C24") (pin "P$2") (pinfunction "2_P$2") (pintype "passive"))
      (node (ref "R73") (pin "P$1") (pinfunction "1_P$1") (pintype "passive"))
      (node (ref "U1") (pin "18") (pinfunction "V3N_18") (pintype "input"))
    )
    (net (code "71") (name "VCP") (class "Default")
      (node (ref "C23") (pin "P$2") (pinfunction "2_P$2") (pintype "passive"))
      (node (ref "R71") (pin "P$1") (pinfunction "1_P$1") (pintype "passive"))
      (node (ref "R72") (pin "P$1") (pinfunction "1_P$1") (pintype "passive"))
      (node (ref "U1") (pin "17") (pinfunction "V3P_17") (pintype "input"))
    )
    (net (code "72") (name "VDD") (class "Default")
      (node (ref "C11") (pin "P$1") (pinfunction "1_P$1") (pintype "passive"))
      (node (ref "C13") (pin "1") (pinfunction "1_1") (pintype "passive"))
      (node (ref "C27") (pin "P$2") (pinfunction "2_P$2") (pintype "passive"))
      (node (ref "C28") (pin "P$2") (pinfunction "2_P$2") (pintype "passive"))
      (node (ref "C64") (pin "P$1") (pinfunction "1_P$1") (pintype "passive"))
      (node (ref "IC2") (pin "3") (pinfunction "OUT_3") (pintype "output"))
      (node (ref "J8") (pin "P$19") (pinfunction "P$19_P$19") (pintype "bidirectional"))
      (node (ref "R1") (pin "P$1") (pinfunction "1_P$1") (pintype "passive"))
      (node (ref "R74") (pin "P$2") (pinfunction "2_P$2") (pintype "passive"))
      (node (ref "U1") (pin "1") (pinfunction "AVDD_1") (pintype "power_in"))
      (node (ref "U1") (pin "48") (pinfunction "DVDD_48") (pintype "power_in"))
    )
    (net (code "73") (name "VDD1P8") (class "Default")
      (node (ref "C29") (pin "P$1") (pinfunction "1_P$1") (pintype "passive"))
      (node (ref "C62") (pin "P$1") (pinfunction "1_P$1") (pintype "passive"))
      (node (ref "U1") (pin "42") (pinfunction "VDD18_2_42") (pintype "power_in"))
      (node (ref "U1") (pin "43") (pinfunction "VDD18_43") (pintype "power_in"))
    )
    (net (code "74") (name "VDD5") (class "Default")
      (node (ref "C14") (pin "P$1") (pinfunction "1_P$1") (pintype "passive"))
      (node (ref "C15") (pin "1") (pinfunction "1_1") (pintype "passive"))
      (node (ref "IC1") (pin "3") (pinfunction "OUT_3") (pintype "output"))
      (node (ref "R4") (pin "P$1") (pinfunction "1_P$1") (pintype "passive"))
    )
    (net (code "75") (name "VREF") (class "Default")
      (node (ref "C25") (pin "P$1") (pinfunction "1_P$1") (pintype "passive"))
      (node (ref "C26") (pin "P$1") (pinfunction "1_P$1") (pintype "passive"))
      (node (ref "U1") (pin "11") (pinfunction "VREF_11") (pintype "output"))
    )
    (net (code "76") (name "WARNOUT") (class "Default")
      (node (ref "J8") (pin "P$9") (pinfunction "P$9_P$9") (pintype "bidirectional"))
      (node (ref "U1") (pin "29") (pinfunction "WARNOUT_29") (pintype "output"))
    )
    (net (code "77") (name "ZX0") (class "Default")
      (node (ref "J8") (pin "P$2") (pinfunction "P$2_P$2") (pintype "bidirectional"))
      (node (ref "U1") (pin "22") (pinfunction "ZX0_22") (pintype "output"))
    )
    (net (code "78") (name "ZX1") (class "Default")
      (node (ref "J8") (pin "P$3") (pinfunction "P$3_P$3") (pintype "bidirectional"))
      (node (ref "U1") (pin "23") (pinfunction "ZX1_23") (pintype "output"))
    )
    (net (code "79") (name "ZX2") (class "Default")
      (node (ref "J8") (pin "P$4") (pinfunction "P$4_P$4") (pintype "bidirectional"))
      (node (ref "U1") (pin "24") (pinfunction "ZX2_24") (pintype "output"))
    )
    (net (code "80") (name "unconnected-(U1-NC-Pad46)") (class "Default")
      (node (ref "U1") (pin "46") (pinfunction "NC_46") (pintype "no_connect"))
    )
    (net (code "81") (name "unconnected-(U1-NC_2-Pad35)") (class "Default")
      (node (ref "U1") (pin "35") (pinfunction "NC_2_35") (pintype "no_connect"))
    )
    (net (code "82") (name "unconnected-(U1-NC_3-Pad45)") (class "Default")
      (node (ref "U1") (pin "45") (pinfunction "NC_3_45") (pintype "no_connect"))
    )
    (net (code "83") (name "unconnected-(U2-NC1-PadP$1)") (class "Default")
      (node (ref "U2") (pin "P$1") (pinfunction "NC1_P$1") (pintype "bidirectional"))
    )
    (net (code "84") (name "unconnected-(U2-NC2-PadP$4)") (class "Default")
      (node (ref "U2") (pin "P$4") (pinfunction "NC2_P$4") (pintype "bidirectional"))
    )
    (net (code "85") (name "unconnected-(U2-NC3-PadP$7)") (class "Default")
      (node (ref "U2") (pin "P$7") (pinfunction "NC3_P$7") (pintype "bidirectional"))
    )
  )
)
